# VUMeterSchematicAltium.net
KiCad netlist of a schematic drawn in Altium Designer
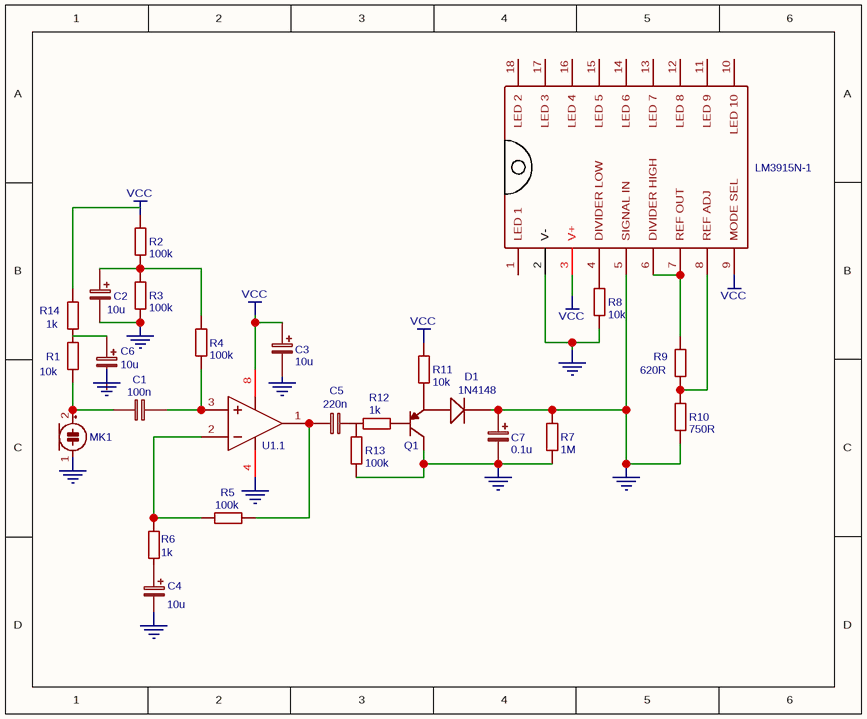
[diagram p0: VUMeterSchematicAltium.schdoc]

(export (version "E")
  (design (tool "Eeschema 10.0.6"))
  (components
    (comp (ref "C1")
      (value "100n")
      (fields (field (name "BOM_MANUFACTURER PART") "?"))
      (libsource (lib "") (part "root_1___1"))
    )
    (comp (ref "C2")
      (value "10u")
      (fields (field (name "BOM_MANUFACTURER PART") "?"))
      (libsource (lib "") (part "root_0___2"))
    )
    (comp (ref "C3")
      (value "10u")
      (fields (field (name "BOM_MANUFACTURER PART") "?"))
      (libsource (lib "") (part "root_0___2"))
    )
    (comp (ref "C4")
      (value "10u")
      (fields (field (name "BOM_MANUFACTURER PART") "?"))
      (libsource (lib "") (part "root_0___2"))
    )
    (comp (ref "C5")
      (value "220n")
      (fields (field (name "BOM_MANUFACTURER PART") "?"))
      (libsource (lib "") (part "root_1___1"))
    )
    (comp (ref "C6")
      (value "10u")
      (fields (field (name "BOM_MANUFACTURER PART") "?"))
      (libsource (lib "") (part "root_0___2"))
    )
    (comp (ref "C7")
      (value "0.1u")
      (fields (field (name "BOM_MANUFACTURER PART") "?"))
      (libsource (lib "") (part "root_0___2"))
    )
    (comp (ref "D1") (value "1N4148") (libsource (lib "altium-import") (part "root_0__")))
    (comp (ref "MK1")
      (value "Microphone_Condenser")
      (fields (field (name "BOM_MANUFACTURER PART") "?") (field (name "CONTRIBUTOR") "KiCAD"))
      (libsource (lib "") (part "root_0___5"))
    )
    (comp (ref "Q1") (value "2N3906") (libsource (lib "") (part "root_0___1")))
    (comp (ref "R1")
      (value "10k")
      (fields (field (name "BOM_MANUFACTURER PART") "?"))
      (libsource (lib "altium-import") (part "root_1__"))
    )
    (comp (ref "R2")
      (value "100k")
      (fields (field (name "BOM_MANUFACTURER PART") "?"))
      (libsource (lib "altium-import") (part "root_1__"))
    )
    (comp (ref "R3")
      (value "100k")
      (fields (field (name "BOM_MANUFACTURER PART") "?"))
      (libsource (lib "altium-import") (part "root_1__"))
    )
    (comp (ref "R4")
      (value "100k")
      (fields (field (name "BOM_MANUFACTURER PART") "?"))
      (libsource (lib "altium-import") (part "root_1__"))
    )
    (comp (ref "R5")
      (value "100k")
      (fields (field (name "BOM_MANUFACTURER PART") "?"))
      (libsource (lib "") (part "root_0___3"))
    )
    (comp (ref "R6")
      (value "1k")
      (fields (field (name "BOM_MANUFACTURER PART") "?"))
      (libsource (lib "altium-import") (part "root_1__"))
    )
    (comp (ref "R7")
      (value "1M")
      (fields (field (name "BOM_MANUFACTURER PART") "?"))
      (libsource (lib "altium-import") (part "root_1__"))
    )
    (comp (ref "R8")
      (value "10k")
      (fields (field (name "BOM_MANUFACTURER PART") "?"))
      (libsource (lib "altium-import") (part "root_1__"))
    )
    (comp (ref "R9")
      (value "620R")
      (fields (field (name "BOM_MANUFACTURER PART") "?"))
      (libsource (lib "altium-import") (part "root_1__"))
    )
    (comp (ref "R10")
      (value "750R")
      (fields (field (name "BOM_MANUFACTURER PART") "?"))
      (libsource (lib "altium-import") (part "root_1__"))
    )
    (comp (ref "R11")
      (value "10k")
      (fields (field (name "BOM_MANUFACTURER PART") "?"))
      (libsource (lib "altium-import") (part "root_1__"))
    )
    (comp (ref "R12")
      (value "1k")
      (fields (field (name "BOM_MANUFACTURER PART") "?"))
      (libsource (lib "") (part "root_0___3"))
    )
    (comp (ref "R13")
      (value "100k")
      (fields (field (name "BOM_MANUFACTURER PART") "?"))
      (libsource (lib "altium-import") (part "root_1__"))
    )
    (comp (ref "R14")
      (value "1k")
      (fields (field (name "BOM_MANUFACTURER PART") "?"))
      (libsource (lib "altium-import") (part "root_1__"))
    )
    (comp (ref "U1.1")
      (value "NE5532AD")
      (fields (field (name "BOM_MANUFACTURER PART") "?"))
      (libsource (lib "") (part "root_0___4"))
    )
    (comp (ref "U2")
      (value "LM3915N-1")
      (description "DotBar Display Driver, 18-pin MDIP")
      (fields (field (name "BOM_MANUFACTURER PART") "?"))
      (libsource (lib "") (part "root_1___2"))
    )
  )
  (nets
    (net (code "1") (name "GND") (class "Default")
      (node (ref "C2") (pin "2") (pinfunction "2_2") (pintype "passive"))
      (node (ref "C7") (pin "1") (pinfunction "1_1") (pintype "passive"))
      (node (ref "C7") (pin "2") (pinfunction "2_2") (pintype "passive"))
      (node (ref "D1") (pin "2") (pinfunction "K_2") (pintype "passive"))
      (node (ref "Q1") (pin "3") (pinfunction "C_3") (pintype "passive"))
      (node (ref "R10") (pin "1") (pinfunction "1_1") (pintype "passive"))
      (node (ref "R13") (pin "1") (pinfunction "1_1") (pintype "passive"))
      (node (ref "R3") (pin "1") (pinfunction "1_1") (pintype "passive"))
      (node (ref "R7") (pin "1") (pinfunction "1_1") (pintype "passive"))
      (node (ref "R7") (pin "2") (pinfunction "2_2") (pintype "passive"))
      (node (ref "R8") (pin "1") (pinfunction "1_1") (pintype "passive"))
      (node (ref "U1.1") (pin "4") (pinfunction "VCC+_4") (pintype "passive"))
      (node (ref "U2") (pin "2") (pinfunction "V-_2") (pintype "passive"))
      (node (ref "U2") (pin "5") (pinfunction "SIGNAL_IN_5") (pintype "passive"))
    )
    (net (code "2") (name "Net-(C2-Pad1)") (class "Default")
      (node (ref "C2") (pin "1") (pinfunction "1_1") (pintype "passive"))
      (node (ref "R2") (pin "1") (pinfunction "1_1") (pintype "passive"))
      (node (ref "R3") (pin "2") (pinfunction "2_2") (pintype "passive"))
      (node (ref "R4") (pin "2") (pinfunction "2_2") (pintype "passive"))
    )
    (net (code "3") (name "Net-(MK1-+)") (class "Default")
      (node (ref "C1") (pin "1") (pinfunction "1_1") (pintype "passive"))
      (node (ref "MK1") (pin "2") (pinfunction "+_2") (pintype "passive"))
      (node (ref "R1") (pin "1") (pinfunction "1_1") (pintype "passive"))
    )
    (net (code "4") (name "Net-(Q1-E)") (class "Default")
      (node (ref "Q1") (pin "1") (pinfunction "E_1") (pintype "passive"))
      (node (ref "R11") (pin "1") (pinfunction "1_1") (pintype "passive"))
    )
    (net (code "5") (name "Net-(U1.1-IN1+)") (class "Default")
      (node (ref "C1") (pin "2") (pinfunction "2_2") (pintype "passive"))
      (node (ref "R4") (pin "1") (pinfunction "1_1") (pintype "passive"))
      (node (ref "U1.1") (pin "3") (pinfunction "IN1+_3") (pintype "passive"))
    )
    (net (code "6") (name "Net-(U1.1-IN1-)") (class "Default")
      (node (ref "R5") (pin "1") (pinfunction "1_1") (pintype "passive"))
      (node (ref "R6") (pin "2") (pinfunction "2_2") (pintype "passive"))
      (node (ref "U1.1") (pin "2") (pinfunction "IN1-_2") (pintype "passive"))
    )
    (net (code "7") (name "Net-(U1.1-OUT1)") (class "Default")
      (node (ref "C5") (pin "1") (pinfunction "1_1") (pintype "passive"))
      (node (ref "R5") (pin "2") (pinfunction "2_2") (pintype "passive"))
      (node (ref "U1.1") (pin "1") (pinfunction "OUT1_1") (pintype "passive"))
    )
    (net (code "8") (name "Net-(U2-DIVIDER_HIGH)") (class "Default")
      (node (ref "R9") (pin "2") (pinfunction "2_2") (pintype "passive"))
      (node (ref "U2") (pin "6") (pinfunction "DIVIDER_HIGH_6") (pintype "passive"))
      (node (ref "U2") (pin "7") (pinfunction "REF_OUT_7") (pintype "passive"))
    )
    (net (code "9") (name "Net-(U2-DIVIDER_LOW)") (class "Default")
      (node (ref "R8") (pin "2") (pinfunction "2_2") (pintype "passive"))
      (node (ref "U2") (pin "4") (pinfunction "DIVIDER_LOW_4") (pintype "passive"))
    )
    (net (code "10") (name "Net-(U2-REF_ADJ)") (class "Default")
      (node (ref "R10") (pin "2") (pinfunction "2_2") (pintype "passive"))
      (node (ref "R9") (pin "1") (pinfunction "1_1") (pintype "passive"))
      (node (ref "U2") (pin "8") (pinfunction "REF_ADJ_8") (pintype "passive"))
    )
    (net (code "11") (name "VCC") (class "Default")
      (node (ref "C3") (pin "1") (pinfunction "1_1") (pintype "passive"))
      (node (ref "R11") (pin "2") (pinfunction "2_2") (pintype "passive"))
      (node (ref "R2") (pin "2") (pinfunction "2_2") (pintype "passive"))
      (node (ref "U1.1") (pin "8") (pinfunction "VCC-_8") (pintype "passive"))
      (node (ref "U2") (pin "3") (pinfunction "V+_3") (pintype "passive"))
      (node (ref "U2") (pin "9") (pinfunction "MODE_SEL_9") (pintype "passive"))
    )
    (net (code "12") (name "unconnected-(C3-Pad2)") (class "Default")
      (node (ref "C3") (pin "2") (pinfunction "2_2") (pintype "passive"))
    )
    (net (code "13") (name "unconnected-(C4-Pad1)") (class "Default")
      (node (ref "C4") (pin "1") (pinfunction "1_1") (pintype "passive"))
    )
    (net (code "14") (name "unconnected-(C4-Pad2)") (class "Default")
      (node (ref "C4") (pin "2") (pinfunction "2_2") (pintype "passive"))
    )
    (net (code "15") (name "unconnected-(C5-Pad2)") (class "Default")
      (node (ref "C5") (pin "2") (pinfunction "2_2") (pintype "passive"))
    )
    (net (code "16") (name "unconnected-(C6-Pad1)") (class "Default")
      (node (ref "C6") (pin "1") (pinfunction "1_1") (pintype "passive"))
    )
    (net (code "17") (name "unconnected-(C6-Pad2)") (class "Default")
      (node (ref "C6") (pin "2") (pinfunction "2_2") (pintype "passive"))
    )
    (net (code "18") (name "unconnected-(D1-A-Pad1)") (class "Default")
      (node (ref "D1") (pin "1") (pinfunction "A_1") (pintype "passive"))
    )
    (net (code "19") (name "unconnected-(MK1---Pad1)") (class "Default")
      (node (ref "MK1") (pin "1") (pinfunction "-_1") (pintype "passive"))
    )
    (net (code "20") (name "unconnected-(Q1-B-Pad2)") (class "Default")
      (node (ref "Q1") (pin "2") (pinfunction "B_2") (pintype "passive"))
    )
    (net (code "21") (name "unconnected-(R1-Pad2)") (class "Default")
      (node (ref "R1") (pin "2") (pinfunction "2_2") (pintype "passive"))
    )
    (net (code "22") (name "unconnected-(R6-Pad1)") (class "Default")
      (node (ref "R6") (pin "1") (pinfunction "1_1") (pintype "passive"))
    )
    (net (code "23") (name "unconnected-(R12-Pad1)") (class "Default")
      (node (ref "R12") (pin "1") (pinfunction "1_1") (pintype "passive"))
    )
    (net (code "24") (name "unconnected-(R12-Pad2)") (class "Default")
      (node (ref "R12") (pin "2") (pinfunction "2_2") (pintype "passive"))
    )
    (net (code "25") (name "unconnected-(R13-Pad2)") (class "Default")
      (node (ref "R13") (pin "2") (pinfunction "2_2") (pintype "passive"))
    )
    (net (code "26") (name "unconnected-(R14-Pad1)") (class "Default")
      (node (ref "R14") (pin "1") (pinfunction "1_1") (pintype "passive"))
    )
    (net (code "27") (name "unconnected-(R14-Pad2)") (class "Default")
      (node (ref "R14") (pin "2") (pinfunction "2_2") (pintype "passive"))
    )
    (net (code "28") (name "unconnected-(U2-LED_1-Pad1)") (class "Default")
      (node (ref "U2") (pin "1") (pinfunction "LED_1_1") (pintype "passive"))
    )
    (net (code "29") (name "unconnected-(U2-LED_2-Pad18)") (class "Default")
      (node (ref "U2") (pin "18") (pinfunction "LED_2_18") (pintype "passive"))
    )
    (net (code "30") (name "unconnected-(U2-LED_3-Pad17)") (class "Default")
      (node (ref "U2") (pin "17") (pinfunction "LED_3_17") (pintype "passive"))
    )
    (net (code "31") (name "unconnected-(U2-LED_4-Pad16)") (class "Default")
      (node (ref "U2") (pin "16") (pinfunction "LED_4_16") (pintype "passive"))
    )
    (net (code "32") (name "unconnected-(U2-LED_5-Pad15)") (class "Default")
      (node (ref "U2") (pin "15") (pinfunction "LED_5_15") (pintype "passive"))
    )
    (net (code "33") (name "unconnected-(U2-LED_6-Pad14)") (class "Default")
      (node (ref "U2") (pin "14") (pinfunction "LED_6_14") (pintype "passive"))
    )
    (net (code "34") (name "unconnected-(U2-LED_7-Pad13)") (class "Default")
      (node (ref "U2") (pin "13") (pinfunction "LED_7_13") (pintype "passive"))
    )
    (net (code "35") (name "unconnected-(U2-LED_8-Pad12)") (class "Default")
      (node (ref "U2") (pin "12") (pinfunction "LED_8_12") (pintype "passive"))
    )
    (net (code "36") (name "unconnected-(U2-LED_9-Pad11)") (class "Default")
      (node (ref "U2") (pin "11") (pinfunction "LED_9_11") (pintype "passive"))
    )
    (net (code "37") (name "unconnected-(U2-LED_10-Pad10)") (class "Default")
      (node (ref "U2") (pin "10") (pinfunction "LED_10_10") (pintype "passive"))
    )
  )
)
